# systems-controller.net
KiCad netlist of a schematic drawn in EAGLE
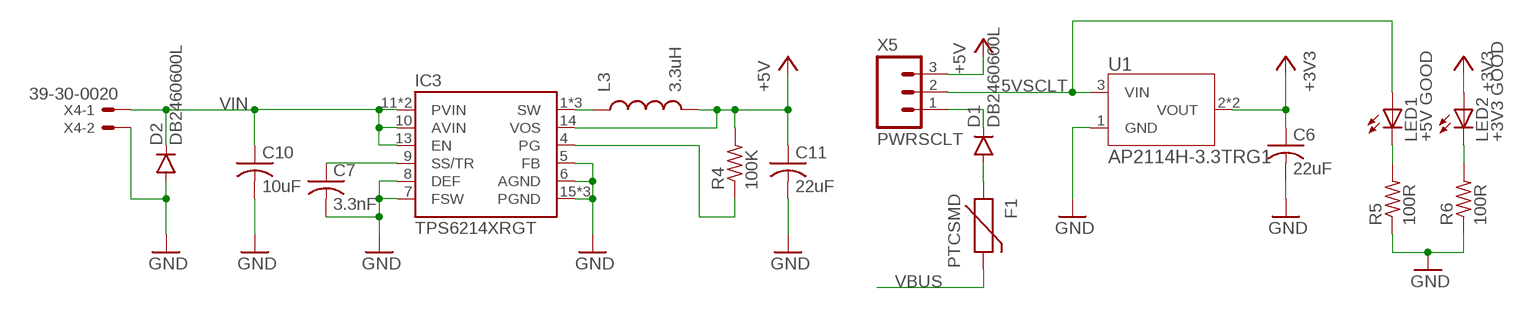
[diagram p0: schematic, sheet 1]
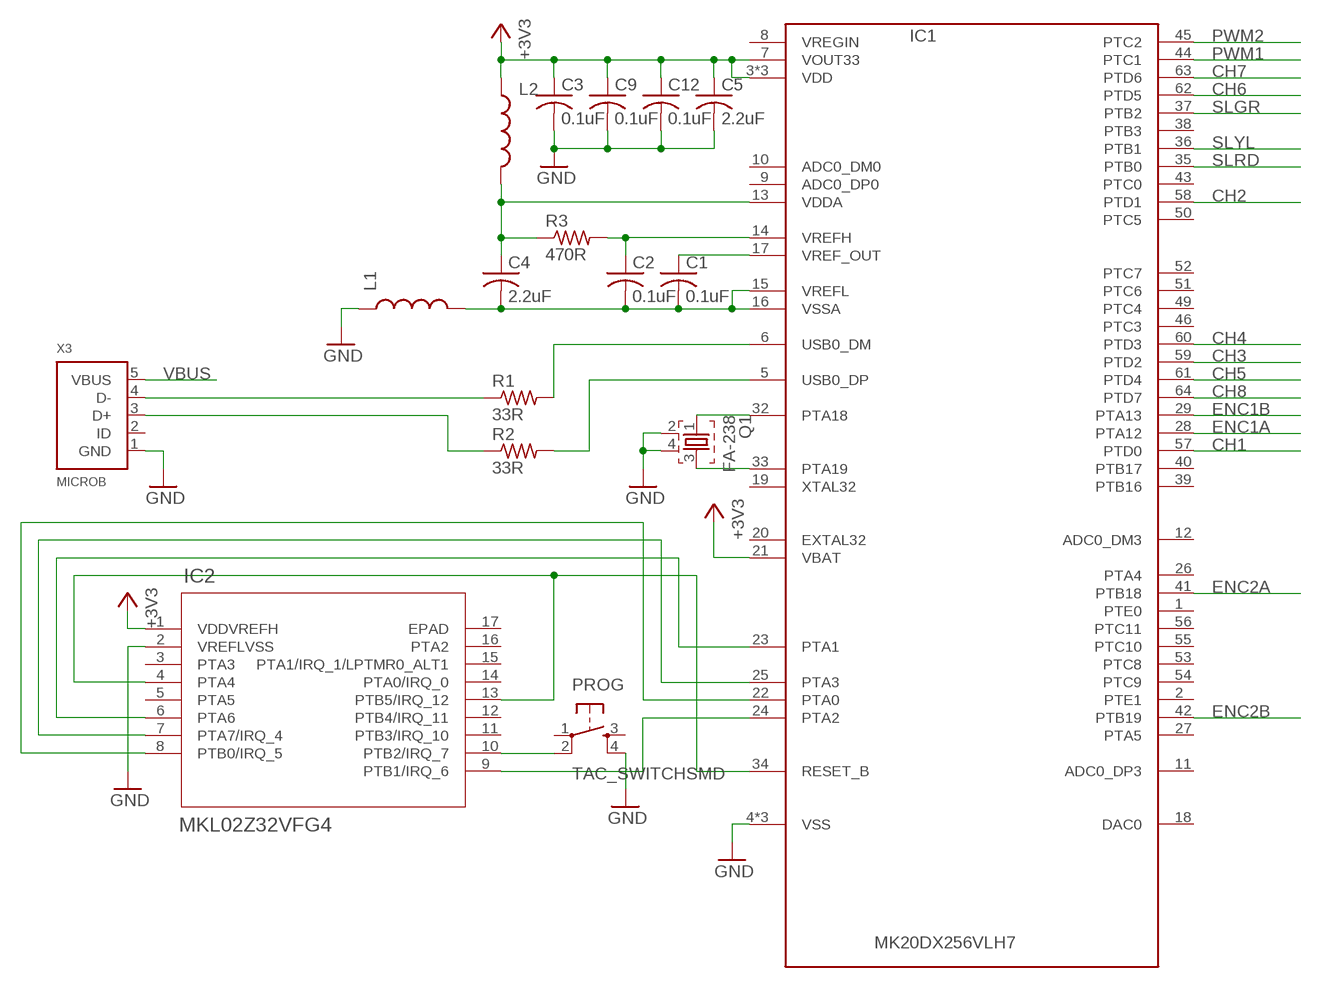
[diagram p1: schematic, sheet 2]
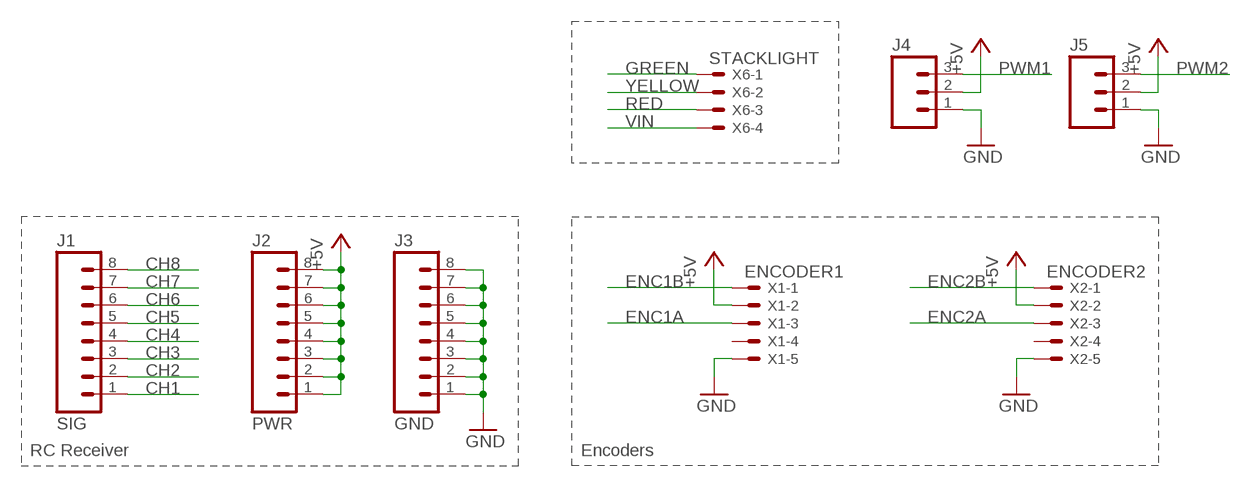
[diagram p2: schematic, sheet 3]
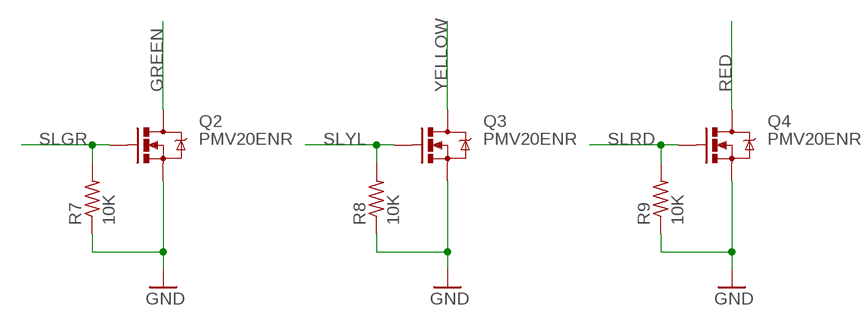
[diagram p3: schematic, sheet 4]

(export (version "E")
  (design (tool "Eeschema 10.0.6"))
  (components
    (comp (ref "J1")
      (value "SIG")
      (footprint "eagle-import:1X08_ROUND")
      (libsource (lib "eagle-import") (part "M08"))
    )
    (comp (ref "J2")
      (value "PWR")
      (footprint "eagle-import:1X08_ROUND")
      (libsource (lib "eagle-import") (part "M08"))
    )
    (comp (ref "J3")
      (value "GND")
      (footprint "eagle-import:1X08_ROUND")
      (libsource (lib "eagle-import") (part "M08"))
    )
    (comp (ref "J4")
      (value "M03PTH")
      (footprint "eagle-import:1X03")
      (libsource (lib "eagle-import") (part "M03PTH"))
    )
    (comp (ref "J5")
      (value "M03PTH")
      (footprint "eagle-import:1X03")
      (libsource (lib "eagle-import") (part "M03PTH"))
    )
    (comp (ref "X1")
      (value "ENCODER1")
      (footprint "eagle-import:70553-05")
      (libsource (lib "eagle-import") (part "C-GRID-05-70553"))
    )
    (comp (ref "X2")
      (value "ENCODER2")
      (footprint "eagle-import:70553-05")
      (libsource (lib "eagle-import") (part "C-GRID-05-70553"))
    )
    (comp (ref "X6")
      (value "STACKLIGHT")
      (footprint "eagle-import:70553-04")
      (libsource (lib "eagle-import") (part "C-GRID-04-70553"))
    )
    (comp (ref "C6")
      (value "22uF")
      (footprint "eagle-import:C0805K")
      (libsource (lib "eagle-import") (part "C-USC0805K"))
    )
    (comp (ref "C7")
      (value "3.3nF")
      (footprint "eagle-import:C0603K")
      (libsource (lib "eagle-import") (part "C-USC0603K"))
    )
    (comp (ref "C10")
      (value "10uF")
      (footprint "eagle-import:C0805K")
      (libsource (lib "eagle-import") (part "C-USC0805K"))
    )
    (comp (ref "C11")
      (value "22uF")
      (footprint "eagle-import:C0805K")
      (libsource (lib "eagle-import") (part "C-USC0805K"))
    )
    (comp (ref "D1")
      (value "DB2460600L")
      (footprint "eagle-import:SOD-128")
      (libsource (lib "eagle-import") (part "DIODESOD128"))
    )
    (comp (ref "D2")
      (value "DB2460600L")
      (footprint "eagle-import:SOD-128")
      (libsource (lib "eagle-import") (part "DIODESOD128"))
    )
    (comp (ref "F1")
      (value "PTCSMD")
      (footprint "eagle-import:PTC-1206")
      (libsource (lib "eagle-import") (part "PTCSMD"))
    )
    (comp (ref "IC3")
      (value "TPS6214XRGT")
      (footprint "eagle-import:16-VQFN")
      (libsource (lib "eagle-import") (part "TPS6214XRGT"))
    )
    (comp (ref "L3")
      (value "3.3uH")
      (footprint "eagle-import:SRN5020")
      (libsource (lib "eagle-import") (part "INDUCTOR-SRN5020"))
    )
    (comp (ref "LED1")
      (value "+5V GOOD")
      (footprint "eagle-import:SML0603")
      (libsource (lib "eagle-import") (part "LEDSML0603"))
    )
    (comp (ref "LED2")
      (value "+3V3 GOOD")
      (footprint "eagle-import:SML0603")
      (libsource (lib "eagle-import") (part "LEDSML0603"))
    )
    (comp (ref "R4")
      (value "100K")
      (footprint "eagle-import:R0603")
      (libsource (lib "eagle-import") (part "R-US_R0603"))
    )
    (comp (ref "R5")
      (value "100R")
      (footprint "eagle-import:R0603")
      (libsource (lib "eagle-import") (part "R-US_R0603"))
    )
    (comp (ref "R6")
      (value "100R")
      (footprint "eagle-import:R0603")
      (libsource (lib "eagle-import") (part "R-US_R0603"))
    )
    (comp (ref "U1")
      (value "AP2114H-3.3TRG1")
      (footprint "eagle-import:SOT-223")
      (fields (field (name "MANUFACTURER_PART_NUMBER") "ap2114h-3.3trg1"))
      (libsource (lib "eagle-import") (part "AP2114H-3.3TRG1"))
    )
    (comp (ref "X4")
      (value "39-30-0020")
      (footprint "eagle-import:39-30-0020")
      (libsource (lib "eagle-import") (part "39-30-0020"))
    )
    (comp (ref "X5")
      (value "PWRSCLT")
      (footprint "eagle-import:1X03")
      (libsource (lib "eagle-import") (part "M03PTH"))
    )
    (comp (ref "Q2")
      (value "PMV20ENR")
      (footprint "eagle-import:SOT23-3")
      (libsource (lib "eagle-import") (part "MOSFET-NCHANNELAO3404A"))
    )
    (comp (ref "Q3")
      (value "PMV20ENR")
      (footprint "eagle-import:SOT23-3")
      (libsource (lib "eagle-import") (part "MOSFET-NCHANNELAO3404A"))
    )
    (comp (ref "Q4")
      (value "PMV20ENR")
      (footprint "eagle-import:SOT23-3")
      (libsource (lib "eagle-import") (part "MOSFET-NCHANNELAO3404A"))
    )
    (comp (ref "R7")
      (value "10K")
      (footprint "eagle-import:R0603")
      (libsource (lib "eagle-import") (part "R-US_R0603"))
    )
    (comp (ref "R8")
      (value "10K")
      (footprint "eagle-import:R0603")
      (libsource (lib "eagle-import") (part "R-US_R0603"))
    )
    (comp (ref "R9")
      (value "10K")
      (footprint "eagle-import:R0603")
      (libsource (lib "eagle-import") (part "R-US_R0603"))
    )
    (comp (ref "C1")
      (value "0.1uF")
      (footprint "eagle-import:C0603K")
      (libsource (lib "eagle-import") (part "C-USC0603K"))
    )
    (comp (ref "C2")
      (value "0.1uF")
      (footprint "eagle-import:C0603K")
      (libsource (lib "eagle-import") (part "C-USC0603K"))
    )
    (comp (ref "C3")
      (value "0.1uF")
      (footprint "eagle-import:C0603K")
      (libsource (lib "eagle-import") (part "C-USC0603K"))
    )
    (comp (ref "C4")
      (value "2.2uF")
      (footprint "eagle-import:C0603K")
      (libsource (lib "eagle-import") (part "C-USC0603K"))
    )
    (comp (ref "C5")
      (value "2.2uF")
      (footprint "eagle-import:C0603K")
      (libsource (lib "eagle-import") (part "C-USC0603K"))
    )
    (comp (ref "C9")
      (value "0.1uF")
      (footprint "eagle-import:C0603K")
      (libsource (lib "eagle-import") (part "C-USC0603K"))
    )
    (comp (ref "C12")
      (value "0.1uF")
      (footprint "eagle-import:C0603K")
      (libsource (lib "eagle-import") (part "C-USC0603K"))
    )
    (comp (ref "IC1")
      (value "MK20DX256VLH7")
      (footprint "eagle-import:MK20DX256VLH7")
      (libsource (lib "eagle-import") (part "MK20DX256VLH7"))
    )
    (comp (ref "IC2")
      (value "MKL02Z32VFG4")
      (footprint "eagle-import:QFN-16_3X3X0.65")
      (fields (field (name "MANUFACTURER_PART_NUMBER") "mkl02z32vfg4"))
      (libsource (lib "eagle-import") (part "MKL02Z32VFG4"))
    )
    (comp (ref "L1")
      (value "INDUCTOR30OHM,1.8A")
      (footprint "eagle-import:0603")
      (libsource (lib "eagle-import") (part "INDUCTOR30OHM,1.8A"))
    )
    (comp (ref "L2")
      (value "INDUCTOR30OHM,1.8A")
      (footprint "eagle-import:0603")
      (libsource (lib "eagle-import") (part "INDUCTOR30OHM,1.8A"))
    )
    (comp (ref "PROG")
      (value "TAC_SWITCHSMD")
      (footprint "eagle-import:TACTILE-SWITCH-SMD")
      (libsource (lib "eagle-import") (part "TAC_SWITCHSMD"))
    )
    (comp (ref "Q1")
      (value "FA-238")
      (footprint "eagle-import:FA-238")
      (libsource (lib "eagle-import") (part "FA-238"))
    )
    (comp (ref "R1")
      (value "33R")
      (footprint "eagle-import:R0603")
      (libsource (lib "eagle-import") (part "R-US_R0603"))
    )
    (comp (ref "R2")
      (value "33R")
      (footprint "eagle-import:R0603")
      (libsource (lib "eagle-import") (part "R-US_R0603"))
    )
    (comp (ref "R3")
      (value "470R")
      (footprint "eagle-import:R0603")
      (libsource (lib "eagle-import") (part "R-US_R0603"))
    )
    (comp (ref "X3")
      (value "MICROB")
      (footprint "eagle-import:10118192")
      (libsource (lib "eagle-import") (part "MICROB"))
    )
  )
  (nets
    (net (code "1") (name "+3V3") (class "Default")
      (node (ref "C12") (pin "1") (pinfunction "1_1") (pintype "passive"))
      (node (ref "C3") (pin "1") (pinfunction "1_1") (pintype "passive"))
      (node (ref "C5") (pin "1") (pinfunction "1_1") (pintype "passive"))
      (node (ref "C6") (pin "1") (pinfunction "1_1") (pintype "passive"))
      (node (ref "C9") (pin "1") (pinfunction "1_1") (pintype "passive"))
      (node (ref "IC1") (pin "21") (pinfunction "VBAT_21") (pintype "bidirectional"))
      (node (ref "IC1") (pin "3") (pinfunction "VDD_3") (pintype "bidirectional"))
      (node (ref "IC1") (pin "30") (pinfunction "VDD_30") (pintype "bidirectional"))
      (node (ref "IC1") (pin "48") (pinfunction "VDD_48") (pintype "bidirectional"))
      (node (ref "IC1") (pin "7") (pinfunction "VOUT33_7") (pintype "bidirectional"))
      (node (ref "IC2") (pin "1") (pinfunction "VDDVREFH_1") (pintype "power_in"))
      (node (ref "L2") (pin "1") (pinfunction "1_1") (pintype "passive"))
      (node (ref "LED2") (pin "A") (pinfunction "A_A") (pintype "passive"))
      (node (ref "U1") (pin "2") (pinfunction "VOUT_2") (pintype "output"))
      (node (ref "U1") (pin "4") (pinfunction "VOUT_4") (pintype "output"))
    )
    (net (code "2") (name "+5V") (class "Default")
      (node (ref "C11") (pin "1") (pinfunction "1_1") (pintype "passive"))
      (node (ref "IC3") (pin "14") (pinfunction "VOS_14") (pintype "input"))
      (node (ref "J2") (pin "1") (pinfunction "1_1") (pintype "passive"))
      (node (ref "J2") (pin "2") (pinfunction "2_2") (pintype "passive"))
      (node (ref "J2") (pin "3") (pinfunction "3_3") (pintype "passive"))
      (node (ref "J2") (pin "4") (pinfunction "4_4") (pintype "passive"))
      (node (ref "J2") (pin "5") (pinfunction "5_5") (pintype "passive"))
      (node (ref "J2") (pin "6") (pinfunction "6_6") (pintype "passive"))
      (node (ref "J2") (pin "7") (pinfunction "7_7") (pintype "passive"))
      (node (ref "J2") (pin "8") (pinfunction "8_8") (pintype "passive"))
      (node (ref "J4") (pin "2") (pinfunction "2_2") (pintype "passive"))
      (node (ref "J5") (pin "2") (pinfunction "2_2") (pintype "passive"))
      (node (ref "L3") (pin "2") (pinfunction "2_2") (pintype "passive"))
      (node (ref "R4") (pin "2") (pinfunction "2_2") (pintype "passive"))
      (node (ref "X1") (pin "2") (pinfunction "S_2") (pintype "passive"))
      (node (ref "X2") (pin "2") (pinfunction "S_2") (pintype "passive"))
      (node (ref "X5") (pin "3") (pinfunction "3_3") (pintype "passive"))
    )
    (net (code "3") (name "5VSCLT") (class "Default")
      (node (ref "LED1") (pin "A") (pinfunction "A_A") (pintype "passive"))
      (node (ref "U1") (pin "3") (pinfunction "VIN_3") (pintype "input"))
      (node (ref "X5") (pin "2") (pinfunction "2_2") (pintype "passive"))
    )
    (net (code "4") (name "CH1") (class "Default")
      (node (ref "IC1") (pin "57") (pinfunction "PTD0_57") (pintype "bidirectional"))
      (node (ref "J1") (pin "1") (pinfunction "1_1") (pintype "passive"))
    )
    (net (code "5") (name "CH2") (class "Default")
      (node (ref "IC1") (pin "58") (pinfunction "PTD1_58") (pintype "bidirectional"))
      (node (ref "J1") (pin "2") (pinfunction "2_2") (pintype "passive"))
    )
    (net (code "6") (name "CH3") (class "Default")
      (node (ref "IC1") (pin "59") (pinfunction "PTD2_59") (pintype "bidirectional"))
      (node (ref "J1") (pin "3") (pinfunction "3_3") (pintype "passive"))
    )
    (net (code "7") (name "CH4") (class "Default")
      (node (ref "IC1") (pin "60") (pinfunction "PTD3_60") (pintype "bidirectional"))
      (node (ref "J1") (pin "4") (pinfunction "4_4") (pintype "passive"))
    )
    (net (code "8") (name "CH5") (class "Default")
      (node (ref "IC1") (pin "61") (pinfunction "PTD4_61") (pintype "bidirectional"))
      (node (ref "J1") (pin "5") (pinfunction "5_5") (pintype "passive"))
    )
    (net (code "9") (name "CH6") (class "Default")
      (node (ref "IC1") (pin "62") (pinfunction "PTD5_62") (pintype "bidirectional"))
      (node (ref "J1") (pin "6") (pinfunction "6_6") (pintype "passive"))
    )
    (net (code "10") (name "CH7") (class "Default")
      (node (ref "IC1") (pin "63") (pinfunction "PTD6_63") (pintype "bidirectional"))
      (node (ref "J1") (pin "7") (pinfunction "7_7") (pintype "passive"))
    )
    (net (code "11") (name "CH8") (class "Default")
      (node (ref "IC1") (pin "64") (pinfunction "PTD7_64") (pintype "bidirectional"))
      (node (ref "J1") (pin "8") (pinfunction "8_8") (pintype "passive"))
    )
    (net (code "12") (name "ENC1A") (class "Default")
      (node (ref "IC1") (pin "28") (pinfunction "PTA12_28") (pintype "bidirectional"))
      (node (ref "X1") (pin "3") (pinfunction "S_3") (pintype "passive"))
    )
    (net (code "13") (name "ENC1B") (class "Default")
      (node (ref "IC1") (pin "29") (pinfunction "PTA13_29") (pintype "bidirectional"))
      (node (ref "X1") (pin "1") (pinfunction "S_1") (pintype "passive"))
    )
    (net (code "14") (name "ENC2A") (class "Default")
      (node (ref "IC1") (pin "41") (pinfunction "PTB18_41") (pintype "bidirectional"))
      (node (ref "X2") (pin "3") (pinfunction "S_3") (pintype "passive"))
    )
    (net (code "15") (name "ENC2B") (class "Default")
      (node (ref "IC1") (pin "42") (pinfunction "PTB19_42") (pintype "bidirectional"))
      (node (ref "X2") (pin "1") (pinfunction "S_1") (pintype "passive"))
    )
    (net (code "16") (name "GND") (class "Default")
      (node (ref "C10") (pin "2") (pinfunction "2_2") (pintype "passive"))
      (node (ref "C11") (pin "2") (pinfunction "2_2") (pintype "passive"))
      (node (ref "C12") (pin "2") (pinfunction "2_2") (pintype "passive"))
      (node (ref "C3") (pin "2") (pinfunction "2_2") (pintype "passive"))
      (node (ref "C5") (pin "2") (pinfunction "2_2") (pintype "passive"))
      (node (ref "C6") (pin "2") (pinfunction "2_2") (pintype "passive"))
      (node (ref "C7") (pin "2") (pinfunction "2_2") (pintype "passive"))
      (node (ref "C9") (pin "2") (pinfunction "2_2") (pintype "passive"))
      (node (ref "D2") (pin "A") (pinfunction "A_A") (pintype "passive"))
      (node (ref "IC1") (pin "31") (pinfunction "VSS_31") (pintype "bidirectional"))
      (node (ref "IC1") (pin "4") (pinfunction "VSS_4") (pintype "bidirectional"))
      (node (ref "IC1") (pin "47") (pinfunction "VSS_47") (pintype "bidirectional"))
      (node (ref "IC2") (pin "2") (pinfunction "VREFLVSS_2") (pintype "power_in"))
      (node (ref "IC3") (pin "15") (pinfunction "PGND_15") (pintype "power_in"))
      (node (ref "IC3") (pin "16") (pinfunction "PGND_16") (pintype "power_in"))
      (node (ref "IC3") (pin "5") (pinfunction "FB_5") (pintype "input"))
      (node (ref "IC3") (pin "6") (pinfunction "AGND_6") (pintype "input"))
      (node (ref "IC3") (pin "7") (pinfunction "FSW_7") (pintype "input"))
      (node (ref "IC3") (pin "8") (pinfunction "DEF_8") (pintype "input"))
      (node (ref "IC3") (pin "PAD") (pinfunction "PGND_PAD") (pintype "power_in"))
      (node (ref "J3") (pin "1") (pinfunction "1_1") (pintype "passive"))
      (node (ref "J3") (pin "2") (pinfunction "2_2") (pintype "passive"))
      (node (ref "J3") (pin "3") (pinfunction "3_3") (pintype "passive"))
      (node (ref "J3") (pin "4") (pinfunction "4_4") (pintype "passive"))
      (node (ref "J3") (pin "5") (pinfunction "5_5") (pintype "passive"))
      (node (ref "J3") (pin "6") (pinfunction "6_6") (pintype "passive"))
      (node (ref "J3") (pin "7") (pinfunction "7_7") (pintype "passive"))
      (node (ref "J3") (pin "8") (pinfunction "8_8") (pintype "passive"))
      (node (ref "J4") (pin "1") (pinfunction "1_1") (pintype "passive"))
      (node (ref "J5") (pin "1") (pinfunction "1_1") (pintype "passive"))
      (node (ref "L1") (pin "1") (pinfunction "1_1") (pintype "passive"))
      (node (ref "PROG") (pin "4") (pinfunction "4_4") (pintype "passive"))
      (node (ref "Q1") (pin "2") (pinfunction "2_2") (pintype "passive"))
      (node (ref "Q1") (pin "4") (pinfunction "4_4") (pintype "passive"))
      (node (ref "Q2") (pin "2") (pinfunction "S_2") (pintype "passive"))
      (node (ref "Q3") (pin "2") (pinfunction "S_2") (pintype "passive"))
      (node (ref "Q4") (pin "2") (pinfunction "S_2") (pintype "passive"))
      (node (ref "R5") (pin "1") (pinfunction "1_1") (pintype "passive"))
      (node (ref "R6") (pin "1") (pinfunction "1_1") (pintype "passive"))
      (node (ref "R7") (pin "1") (pinfunction "1_1") (pintype "passive"))
      (node (ref "R8") (pin "1") (pinfunction "1_1") (pintype "passive"))
      (node (ref "R9") (pin "1") (pinfunction "1_1") (pintype "passive"))
      (node (ref "U1") (pin "1") (pinfunction "GND_1") (pintype "power_in"))
      (node (ref "X1") (pin "5") (pinfunction "S_5") (pintype "passive"))
      (node (ref "X2") (pin "5") (pinfunction "S_5") (pintype "passive"))
      (node (ref "X3") (pin "1") (pinfunction "GND_1") (pintype "bidirectional"))
      (node (ref "X4") (pin "2") (pinfunction "S_2") (pintype "passive"))
    )
    (net (code "17") (name "GREEN") (class "Default")
      (node (ref "Q2") (pin "3") (pinfunction "D_3") (pintype "passive"))
      (node (ref "X6") (pin "1") (pinfunction "S_1") (pintype "passive"))
    )
    (net (code "18") (name "Net-(D1-PadA)") (class "Default")
      (node (ref "D1") (pin "A") (pinfunction "A_A") (pintype "passive"))
      (node (ref "F1") (pin "1") (pinfunction "1_1") (pintype "bidirectional"))
    )
    (net (code "19") (name "Net-(D1-PadC)") (class "Default")
      (node (ref "D1") (pin "C") (pinfunction "C_C") (pintype "passive"))
      (node (ref "X5") (pin "1") (pinfunction "1_1") (pintype "passive"))
    )
    (net (code "20") (name "Net-(IC1-PTA0)") (class "Default")
      (node (ref "IC1") (pin "22") (pinfunction "PTA0_22") (pintype "bidirectional"))
      (node (ref "IC2") (pin "8") (pinfunction "PTB0/IRQ_5_8") (pintype "bidirectional"))
    )
    (net (code "21") (name "Net-(IC1-PTA1)") (class "Default")
      (node (ref "IC1") (pin "23") (pinfunction "PTA1_23") (pintype "bidirectional"))
      (node (ref "IC2") (pin "6") (pinfunction "PTA6_6") (pintype "bidirectional"))
    )
    (net (code "22") (name "Net-(IC1-PTA2)") (class "Default")
      (node (ref "IC1") (pin "24") (pinfunction "PTA2_24") (pintype "bidirectional"))
      (node (ref "IC2") (pin "9") (pinfunction "PTB1/IRQ_6_9") (pintype "bidirectional"))
    )
    (net (code "23") (name "Net-(IC1-PTA3)") (class "Default")
      (node (ref "IC1") (pin "25") (pinfunction "PTA3_25") (pintype "bidirectional"))
      (node (ref "IC2") (pin "7") (pinfunction "PTA7/IRQ_4_7") (pintype "bidirectional"))
    )
    (net (code "24") (name "Net-(IC1-PTA18)") (class "Default")
      (node (ref "IC1") (pin "32") (pinfunction "PTA18_32") (pintype "bidirectional"))
      (node (ref "Q1") (pin "1") (pinfunction "1_1") (pintype "passive"))
    )
    (net (code "25") (name "Net-(IC1-PTA19)") (class "Default")
      (node (ref "IC1") (pin "33") (pinfunction "PTA19_33") (pintype "bidirectional"))
      (node (ref "Q1") (pin "3") (pinfunction "3_3") (pintype "passive"))
    )
    (net (code "26") (name "Net-(IC1-RESET_B)") (class "Default")
      (node (ref "IC1") (pin "34") (pinfunction "RESET_B_34") (pintype "bidirectional"))
      (node (ref "IC2") (pin "13") (pinfunction "PTB5/IRQ_12_13") (pintype "bidirectional"))
      (node (ref "IC2") (pin "4") (pinfunction "PTA4_4") (pintype "bidirectional"))
    )
    (net (code "27") (name "Net-(IC1-USB0_DM)") (class "Default")
      (node (ref "IC1") (pin "6") (pinfunction "USB0_DM_6") (pintype "bidirectional"))
      (node (ref "R1") (pin "2") (pinfunction "2_2") (pintype "passive"))
    )
    (net (code "28") (name "Net-(IC1-USB0_DP)") (class "Default")
      (node (ref "IC1") (pin "5") (pinfunction "USB0_DP_5") (pintype "bidirectional"))
      (node (ref "R2") (pin "2") (pinfunction "2_2") (pintype "passive"))
    )
    (net (code "29") (name "Net-(IC1-VDDA)") (class "Default")
      (node (ref "C4") (pin "1") (pinfunction "1_1") (pintype "passive"))
      (node (ref "IC1") (pin "13") (pinfunction "VDDA_13") (pintype "bidirectional"))
      (node (ref "L2") (pin "2") (pinfunction "2_2") (pintype "passive"))
      (node (ref "R3") (pin "1") (pinfunction "1_1") (pintype "passive"))
    )
    (net (code "30") (name "Net-(IC1-VREFH)") (class "Default")
      (node (ref "C2") (pin "1") (pinfunction "1_1") (pintype "passive"))
      (node (ref "IC1") (pin "14") (pinfunction "VREFH_14") (pintype "bidirectional"))
      (node (ref "R3") (pin "2") (pinfunction "2_2") (pintype "passive"))
    )
    (net (code "31") (name "Net-(IC1-VREFL)") (class "Default")
      (node (ref "C1") (pin "2") (pinfunction "2_2") (pintype "passive"))
      (node (ref "C2") (pin "2") (pinfunction "2_2") (pintype "passive"))
      (node (ref "C4") (pin "2") (pinfunction "2_2") (pintype "passive"))
      (node (ref "IC1") (pin "15") (pinfunction "VREFL_15") (pintype "bidirectional"))
      (node (ref "IC1") (pin "16") (pinfunction "VSSA_16") (pintype "bidirectional"))
      (node (ref "L1") (pin "2") (pinfunction "2_2") (pintype "passive"))
    )
    (net (code "32") (name "Net-(IC1-VREF_OUT)") (class "Default")
      (node (ref "C1") (pin "1") (pinfunction "1_1") (pintype "passive"))
      (node (ref "IC1") (pin "17") (pinfunction "VREF_OUT_17") (pintype "bidirectional"))
    )
    (net (code "33") (name "Net-(IC2-PTB2{slash}IRQ_7)") (class "Default")
      (node (ref "IC2") (pin "10") (pinfunction "PTB2/IRQ_7_10") (pintype "bidirectional"))
      (node (ref "PROG") (pin "2") (pinfunction "2_2") (pintype "passive"))
    )
    (net (code "34") (name "Net-(IC3-PG)") (class "Default")
      (node (ref "IC3") (pin "4") (pinfunction "PG_4") (pintype "output"))
      (node (ref "R4") (pin "1") (pinfunction "1_1") (pintype "passive"))
    )
    (net (code "35") (name "Net-(IC3-SS{slash}TR)") (class "Default")
      (node (ref "C7") (pin "1") (pinfunction "1_1") (pintype "passive"))
      (node (ref "IC3") (pin "9") (pinfunction "SS/TR_9") (pintype "input"))
    )
    (net (code "36") (name "Net-(IC3-SW-Pad1)") (class "Default")
      (node (ref "IC3") (pin "1") (pinfunction "SW_1") (pintype "output"))
      (node (ref "IC3") (pin "2") (pinfunction "SW_2") (pintype "output"))
      (node (ref "IC3") (pin "3") (pinfunction "SW_3") (pintype "output"))
      (node (ref "L3") (pin "1") (pinfunction "1_1") (pintype "passive"))
    )
    (net (code "37") (name "Net-(LED1-PadC)") (class "Default")
      (node (ref "LED1") (pin "C") (pinfunction "C_C") (pintype "passive"))
      (node (ref "R5") (pin "2") (pinfunction "2_2") (pintype "passive"))
    )
    (net (code "38") (name "Net-(LED2-PadC)") (class "Default")
      (node (ref "LED2") (pin "C") (pinfunction "C_C") (pintype "passive"))
      (node (ref "R6") (pin "2") (pinfunction "2_2") (pintype "passive"))
    )
    (net (code "39") (name "Net-(X3-D+)") (class "Default")
      (node (ref "R2") (pin "1") (pinfunction "1_1") (pintype "passive"))
      (node (ref "X3") (pin "3") (pinfunction "D+_3") (pintype "bidirectional"))
    )
    (net (code "40") (name "Net-(X3-D-)") (class "Default")
      (node (ref "R1") (pin "1") (pinfunction "1_1") (pintype "passive"))
      (node (ref "X3") (pin "4") (pinfunction "D-_4") (pintype "bidirectional"))
    )
    (net (code "41") (name "PWM1") (class "Default")
      (node (ref "IC1") (pin "44") (pinfunction "PTC1_44") (pintype "bidirectional"))
      (node (ref "J4") (pin "3") (pinfunction "3_3") (pintype "passive"))
    )
    (net (code "42") (name "PWM2") (class "Default")
      (node (ref "IC1") (pin "45") (pinfunction "PTC2_45") (pintype "bidirectional"))
      (node (ref "J5") (pin "3") (pinfunction "3_3") (pintype "passive"))
    )
    (net (code "43") (name "RED") (class "Default")
      (node (ref "Q4") (pin "3") (pinfunction "D_3") (pintype "passive"))
      (node (ref "X6") (pin "3") (pinfunction "S_3") (pintype "passive"))
    )
    (net (code "44") (name "SLGR") (class "Default")
      (node (ref "IC1") (pin "37") (pinfunction "PTB2_37") (pintype "bidirectional"))
      (node (ref "Q2") (pin "1") (pinfunction "G_1") (pintype "passive"))
      (node (ref "R7") (pin "2") (pinfunction "2_2") (pintype "passive"))
    )
    (net (code "45") (name "SLRD") (class "Default")
      (node (ref "IC1") (pin "35") (pinfunction "PTB0_35") (pintype "bidirectional"))
      (node (ref "Q4") (pin "1") (pinfunction "G_1") (pintype "passive"))
      (node (ref "R9") (pin "2") (pinfunction "2_2") (pintype "passive"))
    )
    (net (code "46") (name "SLYL") (class "Default")
      (node (ref "IC1") (pin "36") (pinfunction "PTB1_36") (pintype "bidirectional"))
      (node (ref "Q3") (pin "1") (pinfunction "G_1") (pintype "passive"))
      (node (ref "R8") (pin "2") (pinfunction "2_2") (pintype "passive"))
    )
    (net (code "47") (name "VBUS") (class "Default")
      (node (ref "F1") (pin "2") (pinfunction "2_2") (pintype "bidirectional"))
      (node (ref "X3") (pin "5") (pinfunction "VBUS_5") (pintype "bidirectional"))
    )
    (net (code "48") (name "VIN") (class "Default")
      (node (ref "C10") (pin "1") (pinfunction "1_1") (pintype "passive"))
      (node (ref "D2") (pin "C") (pinfunction "C_C") (pintype "passive"))
      (node (ref "IC3") (pin "10") (pinfunction "AVIN_10") (pintype "input"))
      (node (ref "IC3") (pin "11") (pinfunction "PVIN_11") (pintype "input"))
      (node (ref "IC3") (pin "12") (pinfunction "PVIN_12") (pintype "input"))
      (node (ref "IC3") (pin "13") (pinfunction "EN_13") (pintype "input"))
      (node (ref "X4") (pin "1") (pinfunction "S_1") (pintype "passive"))
      (node (ref "X6") (pin "4") (pinfunction "S_4") (pintype "passive"))
    )
    (net (code "49") (name "YELLOW") (class "Default")
      (node (ref "Q3") (pin "3") (pinfunction "D_3") (pintype "passive"))
      (node (ref "X6") (pin "2") (pinfunction "S_2") (pintype "passive"))
    )
    (net (code "50") (name "unconnected-(IC1-ADC0_DM0-Pad10)") (class "Default")
      (node (ref "IC1") (pin "10") (pinfunction "ADC0_DM0_10") (pintype "bidirectional"))
    )
    (net (code "51") (name "unconnected-(IC1-ADC0_DM3-Pad12)") (class "Default")
      (node (ref "IC1") (pin "12") (pinfunction "ADC0_DM3_12") (pintype "bidirectional"))
    )
    (net (code "52") (name "unconnected-(IC1-ADC0_DP0-Pad9)") (class "Default")
      (node (ref "IC1") (pin "9") (pinfunction "ADC0_DP0_9") (pintype "bidirectional"))
    )
    (net (code "53") (name "unconnected-(IC1-ADC0_DP3-Pad11)") (class "Default")
      (node (ref "IC1") (pin "11") (pinfunction "ADC0_DP3_11") (pintype "bidirectional"))
    )
    (net (code "54") (name "unconnected-(IC1-DAC0-Pad18)") (class "Default")
      (node (ref "IC1") (pin "18") (pinfunction "DAC0_18") (pintype "bidirectional"))
    )
    (net (code "55") (name "unconnected-(IC1-EXTAL32-Pad20)") (class "Default")
      (node (ref "IC1") (pin "20") (pinfunction "EXTAL32_20") (pintype "bidirectional"))
    )
    (net (code "56") (name "unconnected-(IC1-PTA4-Pad26)") (class "Default")
      (node (ref "IC1") (pin "26") (pinfunction "PTA4_26") (pintype "bidirectional"))
    )
    (net (code "57") (name "unconnected-(IC1-PTA5-Pad27)") (class "Default")
      (node (ref "IC1") (pin "27") (pinfunction "PTA5_27") (pintype "bidirectional"))
    )
    (net (code "58") (name "unconnected-(IC1-PTB3-Pad38)") (class "Default")
      (node (ref "IC1") (pin "38") (pinfunction "PTB3_38") (pintype "bidirectional"))
    )
    (net (code "59") (name "unconnected-(IC1-PTB16-Pad39)") (class "Default")
      (node (ref "IC1") (pin "39") (pinfunction "PTB16_39") (pintype "bidirectional"))
    )
    (net (code "60") (name "unconnected-(IC1-PTB17-Pad40)") (class "Default")
      (node (ref "IC1") (pin "40") (pinfunction "PTB17_40") (pintype "bidirectional"))
    )
    (net (code "61") (name "unconnected-(IC1-PTC0-Pad43)") (class "Default")
      (node (ref "IC1") (pin "43") (pinfunction "PTC0_43") (pintype "bidirectional"))
    )
    (net (code "62") (name "unconnected-(IC1-PTC3-Pad46)") (class "Default")
      (node (ref "IC1") (pin "46") (pinfunction "PTC3_46") (pintype "bidirectional"))
    )
    (net (code "63") (name "unconnected-(IC1-PTC4-Pad49)") (class "Default")
      (node (ref "IC1") (pin "49") (pinfunction "PTC4_49") (pintype "bidirectional"))
    )
    (net (code "64") (name "unconnected-(IC1-PTC5-Pad50)") (class "Default")
      (node (ref "IC1") (pin "50") (pinfunction "PTC5_50") (pintype "bidirectional"))
    )
    (net (code "65") (name "unconnected-(IC1-PTC6-Pad51)") (class "Default")
      (node (ref "IC1") (pin "51") (pinfunction "PTC6_51") (pintype "bidirectional"))
    )
    (net (code "66") (name "unconnected-(IC1-PTC7-Pad52)") (class "Default")
      (node (ref "IC1") (pin "52") (pinfunction "PTC7_52") (pintype "bidirectional"))
    )
    (net (code "67") (name "unconnected-(IC1-PTC8-Pad53)") (class "Default")
      (node (ref "IC1") (pin "53") (pinfunction "PTC8_53") (pintype "bidirectional"))
    )
    (net (code "68") (name "unconnected-(IC1-PTC9-Pad54)") (class "Default")
      (node (ref "IC1") (pin "54") (pinfunction "PTC9_54") (pintype "bidirectional"))
    )
    (net (code "69") (name "unconnected-(IC1-PTC10-Pad55)") (class "Default")
      (node (ref "IC1") (pin "55") (pinfunction "PTC10_55") (pintype "bidirectional"))
    )
    (net (code "70") (name "unconnected-(IC1-PTC11-Pad56)") (class "Default")
      (node (ref "IC1") (pin "56") (pinfunction "PTC11_56") (pintype "bidirectional"))
    )
    (net (code "71") (name "unconnected-(IC1-PTE0-Pad1)") (class "Default")
      (node (ref "IC1") (pin "1") (pinfunction "PTE0_1") (pintype "bidirectional"))
    )
    (net (code "72") (name "unconnected-(IC1-PTE1-Pad2)") (class "Default")
      (node (ref "IC1") (pin "2") (pinfunction "PTE1_2") (pintype "bidirectional"))
    )
    (net (code "73") (name "unconnected-(IC1-VREGIN-Pad8)") (class "Default")
      (node (ref "IC1") (pin "8") (pinfunction "VREGIN_8") (pintype "bidirectional"))
    )
    (net (code "74") (name "unconnected-(IC1-XTAL32-Pad19)") (class "Default")
      (node (ref "IC1") (pin "19") (pinfunction "XTAL32_19") (pintype "bidirectional"))
    )
    (net (code "75") (name "unconnected-(IC2-EPAD-Pad17)") (class "Default")
      (node (ref "IC2") (pin "17") (pinfunction "EPAD_17") (pintype "passive"))
    )
    (net (code "76") (name "unconnected-(IC2-PTA0{slash}IRQ_0-Pad14)") (class "Default")
      (node (ref "IC2") (pin "14") (pinfunction "PTA0/IRQ_0_14") (pintype "bidirectional"))
    )
    (net (code "77") (name "unconnected-(IC2-PTA1{slash}IRQ_1{slash}LPTMR0_ALT1-Pad15)") (class "Default")
      (node (ref "IC2") (pin "15") (pinfunction "PTA1/IRQ_1/LPTMR0_ALT1_15") (pintype "bidirectional"))
    )
    (net (code "78") (name "unconnected-(IC2-PTA2-Pad16)") (class "Default")
      (node (ref "IC2") (pin "16") (pinfunction "PTA2_16") (pintype "bidirectional"))
    )
    (net (code "79") (name "unconnected-(IC2-PTA3-Pad3)") (class "Default")
      (node (ref "IC2") (pin "3") (pinfunction "PTA3_3") (pintype "bidirectional"))
    )
    (net (code "80") (name "unconnected-(IC2-PTA5-Pad5)") (class "Default")
      (node (ref "IC2") (pin "5") (pinfunction "PTA5_5") (pintype "bidirectional"))
    )
    (net (code "81") (name "unconnected-(IC2-PTB3{slash}IRQ_10-Pad11)") (class "Default")
      (node (ref "IC2") (pin "11") (pinfunction "PTB3/IRQ_10_11") (pintype "bidirectional"))
    )
    (net (code "82") (name "unconnected-(IC2-PTB4{slash}IRQ_11-Pad12)") (class "Default")
      (node (ref "IC2") (pin "12") (pinfunction "PTB4/IRQ_11_12") (pintype "bidirectional"))
    )
    (net (code "83") (name "unconnected-(PROG-Pad1)") (class "Default")
      (node (ref "PROG") (pin "1") (pinfunction "1_1") (pintype "passive"))
    )
    (net (code "84") (name "unconnected-(PROG-Pad3)") (class "Default")
      (node (ref "PROG") (pin "3") (pinfunction "3_3") (pintype "passive"))
    )
    (net (code "85") (name "unconnected-(X1D-S-Pad4)") (class "Default")
      (node (ref "X1") (pin "4") (pinfunction "S_4") (pintype "passive"))
    )
    (net (code "86") (name "unconnected-(X2D-S-Pad4)") (class "Default")
      (node (ref "X2") (pin "4") (pinfunction "S_4") (pintype "passive"))
    )
    (net (code "87") (name "unconnected-(X3-ID-Pad2)") (class "Default")
      (node (ref "X3") (pin "2") (pinfunction "ID_2") (pintype "bidirectional"))
    )
  )
)
